# interface.net
KiCad netlist of a schematic drawn in Altium Designer
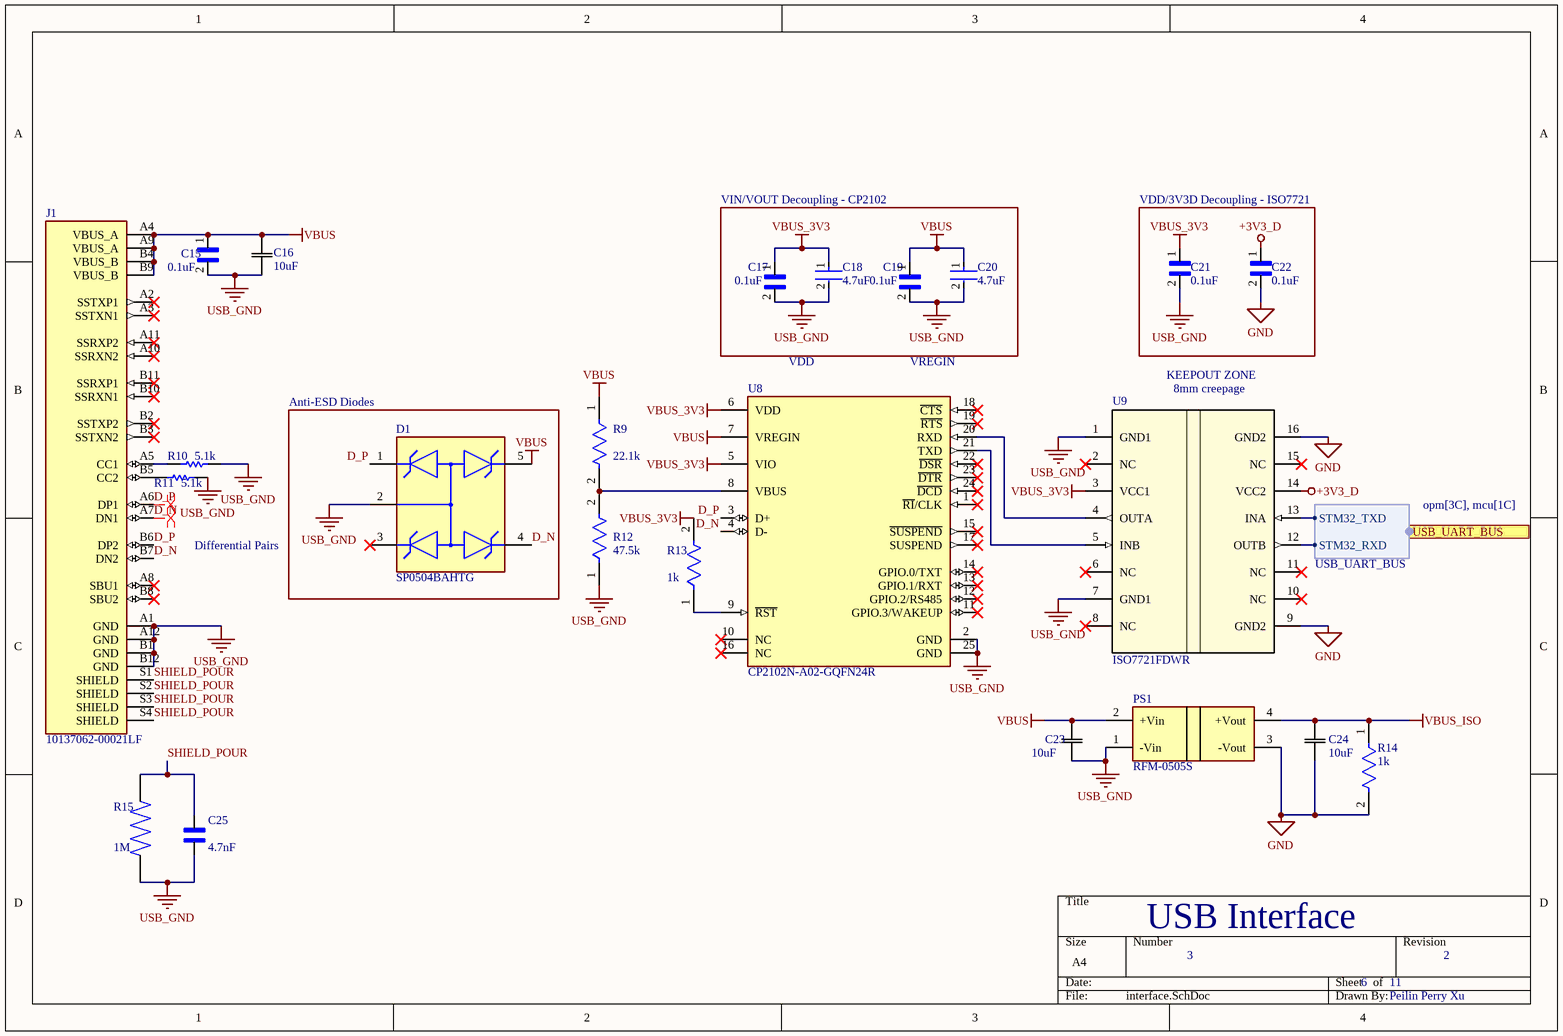
[diagram p0: interface.SchDoc]

(export (version "E")
  (design (tool "Eeschema 10.0.6"))
  (components
    (comp (ref "C15")
      (value "0.1uF")
      (footprint "CC0603JRX7R8BB104")
      (description "25V 100nF X7R ±5% 0603 Multilayer Ceramic Capacitors MLCC - SMD/SMT ROHS")
      (fields
        (field (name "MANUFACTURER") "Yageo Group")
        (field (name "MANUFACTURER PART NUMBER") "CC0603JRX7R8BB104")
      )
      (libsource (lib "opm_lib") (part "CC0603JRX7R8BB104"))
    )
    (comp (ref "C16")
      (value "10uF")
      (footprint "CC0805KKX7R7BB106")
      (description "16V 10uF X7R ±10% 0805 Multilayer Ceramic Capacitors MLCC - SMD/SMT ROHS")
      (fields
        (field (name "MANUFACTURER") "Yageo Group")
        (field (name "MANUFACTURER PART NUMBER") "CC0805KKX7R7BB106")
      )
      (libsource (lib "opm_lib") (part "CC0805KKX7R7BB106"))
    )
    (comp (ref "C17")
      (value "0.1uF")
      (footprint "CC0603JRX7R8BB104")
      (description "25V 100nF X7R ±5% 0603 Multilayer Ceramic Capacitors MLCC - SMD/SMT ROHS")
      (fields
        (field (name "MANUFACTURER") "Yageo Group")
        (field (name "MANUFACTURER PART NUMBER") "CC0603JRX7R8BB104")
      )
      (libsource (lib "opm_lib") (part "CC0603JRX7R8BB104"))
    )
    (comp (ref "C18")
      (value "4.7uF")
      (footprint "CC0805KKX7R7BB106")
      (description "16V 4.7uF X7R ±10% 0805 Multilayer Ceramic Capacitors MLCC - SMD/SMT ROHS")
      (fields
        (field (name "MANUFACTURER") "Yageo Group")
        (field (name "MANUFACTURER PART NUMBER") "CC0805KKX7R7BB475")
      )
      (libsource (lib "opm_lib") (part "CC0805KKX7R7BB475"))
    )
    (comp (ref "C19")
      (value "0.1uF")
      (footprint "CC0603JRX7R8BB104")
      (description "25V 100nF X7R ±5% 0603 Multilayer Ceramic Capacitors MLCC - SMD/SMT ROHS")
      (fields
        (field (name "MANUFACTURER") "Yageo Group")
        (field (name "MANUFACTURER PART NUMBER") "CC0603JRX7R8BB104")
      )
      (libsource (lib "opm_lib") (part "CC0603JRX7R8BB104"))
    )
    (comp (ref "C20")
      (value "4.7uF")
      (footprint "CC0805KKX7R7BB106")
      (description "16V 4.7uF X7R ±10% 0805 Multilayer Ceramic Capacitors MLCC - SMD/SMT ROHS")
      (fields
        (field (name "MANUFACTURER") "Yageo Group")
        (field (name "MANUFACTURER PART NUMBER") "CC0805KKX7R7BB475")
      )
      (libsource (lib "opm_lib") (part "CC0805KKX7R7BB475"))
    )
    (comp (ref "C21")
      (value "0.1uF")
      (footprint "CC0603JRX7R8BB104")
      (description "25V 100nF X7R ±5% 0603 Multilayer Ceramic Capacitors MLCC - SMD/SMT ROHS")
      (fields
        (field (name "MANUFACTURER") "Yageo Group")
        (field (name "MANUFACTURER PART NUMBER") "CC0603JRX7R8BB104")
      )
      (libsource (lib "opm_lib") (part "CC0603JRX7R8BB104"))
    )
    (comp (ref "C22")
      (value "0.1uF")
      (footprint "CC0603JRX7R8BB104")
      (description "25V 100nF X7R ±5% 0603 Multilayer Ceramic Capacitors MLCC - SMD/SMT ROHS")
      (fields
        (field (name "MANUFACTURER") "Yageo Group")
        (field (name "MANUFACTURER PART NUMBER") "CC0603JRX7R8BB104")
      )
      (libsource (lib "opm_lib") (part "CC0603JRX7R8BB104"))
    )
    (comp (ref "C23")
      (value "10uF")
      (footprint "CC0805KKX7R7BB106")
      (description "16V 10uF X7R ±10% 0805 Multilayer Ceramic Capacitors MLCC - SMD/SMT ROHS")
      (fields
        (field (name "MANUFACTURER") "Yageo Group")
        (field (name "MANUFACTURER PART NUMBER") "CC0805KKX7R7BB106")
      )
      (libsource (lib "opm_lib") (part "CC0805KKX7R7BB106"))
    )
    (comp (ref "C24")
      (value "10uF")
      (footprint "CC0805KKX7R7BB106")
      (description "16V 10uF X7R ±10% 0805 Multilayer Ceramic Capacitors MLCC - SMD/SMT ROHS")
      (fields
        (field (name "MANUFACTURER") "Yageo Group")
        (field (name "MANUFACTURER PART NUMBER") "CC0805KKX7R7BB106")
      )
      (libsource (lib "opm_lib") (part "CC0805KKX7R7BB106"))
    )
    (comp (ref "C25")
      (value "4.7nF")
      (footprint "CAPC3216X170N")
      (description "Multilayer Ceramic Capacitor, 4700 pF, 500 V, ± 10%, X7R, 1206 [3216 Metric]")
      (fields
        (field (name "MANUFACTURER") "Vishay")
        (field (name "MANUFACTURER PART NUMBER") "VJ1206Y472KXEAT5Z")
      )
      (libsource (lib "opm_lib") (part "VJ1206Y472KXEAT5Z"))
    )
    (comp (ref "D1")
      (value "SP0504BAHTG")
      (footprint "SP0504BAHTG")
      (description "SP050xBA Series 8 V 30 pF Uni-Directional SMT TVS Avalanche Diode Array SOT-23-5")
      (fields (field (name "MANUFACTURER") "Littelfuse"))
      (libsource (lib "opm_lib") (part "SP0504BAHTG"))
    )
    (comp (ref "J1")
      (value "10137062-00021LF")
      (footprint "AMPHENOL_10137062-00021LF")
      (description "Conn USB Type C Receptacle 24 POS 0.5mm RA Surface Mount/Through Hole Single Port T/R")
      (fields (field (name "MANUFACTURER") "Amphenol Communications Solutions"))
      (libsource (lib "opm_lib") (part "10137062-00021LF"))
    )
    (comp (ref "PS1")
      (value "RFM-0505S")
      (footprint "RFM-0505S")
      (description "DC/DC Converter ; 1W; Vin: 4.5-5.5V; Vout: 5V; Iout: 20mA; -40+85deg.C; THT; SIP4")
      (fields (field (name "MANUFACTURER") "Recom Power"))
      (libsource (lib "opm_lib") (part "RFM-0505S"))
    )
    (comp (ref "R9")
      (value "22.1k")
      (footprint "RC0603FR-07")
      (description "Res General Purpose Thick Film 0603 22.1K Ohm 1% 1/10W ±100ppm/°C Molded SMD Paper T/R")
      (fields
        (field (name "MANUFACTURER") "Yageo Group")
        (field (name "MANUFACTURER PART NUMBER") "RC0603FR-0722K1L")
      )
      (libsource (lib "opm_lib") (part "RC0603FR-0722K1L"))
    )
    (comp (ref "R10")
      (value "5.1k")
      (footprint "RC0603FR-07")
      (description "Res Thick Film 0603 5.1K Ohm 1% 0.1W(1/10W) ±100ppm/C Pad SMD T/R")
      (fields
        (field (name "MANUFACTURER") "Yageo Group")
        (field (name "MANUFACTURER PART NUMBER") "RC0603FR-075K1L")
      )
      (libsource (lib "opm_lib") (part "RC0603FR-075K1L"))
    )
    (comp (ref "R11")
      (value "5.1k")
      (footprint "RC0603FR-07")
      (description "Res Thick Film 0603 5.1K Ohm 1% 0.1W(1/10W) ±100ppm/C Pad SMD T/R")
      (fields
        (field (name "MANUFACTURER") "Yageo Group")
        (field (name "MANUFACTURER PART NUMBER") "RC0603FR-075K1L")
      )
      (libsource (lib "opm_lib") (part "RC0603FR-075K1L"))
    )
    (comp (ref "R12")
      (value "47.5k")
      (footprint "RC0603FR-07")
      (description "100mW Thick Film Resistors 75V ±100ppm/℃ ±1% 47.5kΩ 0603 Chip Resistor - Surface Mount ROHS")
      (fields
        (field (name "MANUFACTURER") "Yageo Group")
        (field (name "MANUFACTURER PART NUMBER") "RC0603FR-0747K5L")
      )
      (libsource (lib "opm_lib") (part "RC0603FR-0747K5L"))
    )
    (comp (ref "R13")
      (value "1k")
      (footprint "RC0603FR-07")
      (description "100mW Thick Film Resistors 75V ±100ppm/℃ ±1% 1kΩ 0603 Chip Resistor - Surface Mount ROHS")
      (fields
        (field (name "MANUFACTURER") "Yageo Group")
        (field (name "MANUFACTURER PART NUMBER") "RC0603FR-071KL")
      )
      (libsource (lib "opm_lib") (part "RC0603FR-071KL"))
    )
    (comp (ref "R14")
      (value "1k")
      (footprint "RC0603FR-07")
      (description "100mW Thick Film Resistors 75V ±100ppm/℃ ±1% 1kΩ 0603 Chip Resistor - Surface Mount ROHS")
      (fields
        (field (name "MANUFACTURER") "Yageo Group")
        (field (name "MANUFACTURER PART NUMBER") "RC0603FR-071KL")
      )
      (libsource (lib "opm_lib") (part "RC0603FR-071KL"))
    )
    (comp (ref "R15")
      (value "1M")
      (footprint "RESC2012X50N")
      (description "Res Thick Film 0805 1M Ohm 1% 0.125W(1/8W) +/-100ppm/ßC Pad SMD Automotive T/R")
      (fields
        (field (name "MANUFACTURER") "Vishay")
        (field (name "MANUFACTURER PART NUMBER") "CRCW08051M00FKEA")
      )
      (libsource (lib "opm_lib") (part "CRCW08051M00FKEA"))
    )
    (comp (ref "U8")
      (value "CP2102N-A02-GQFN24R")
      (footprint "CP2102N-A02-GQFN24R")
      (description "Full Speed USB to UART Bridge USB 2.0 3.3V T/R Automotive Medical 24-Pin QFN EP")
      (fields (field (name "MANUFACTURER") "Silicon Lab"))
      (libsource (lib "opm_lib") (part "CP2102N-A02-GQFN24R"))
    )
    (comp (ref "U9")
      (value "ISO7721FDWR")
      (footprint "ISO7721FDWR")
      (description "Robust EMC, dual-channel, 1/1, reinforced digital isolator 16-SOIC -55 to 125")
      (fields (field (name "MANUFACTURER") "Texas Instruments"))
      (libsource (lib "opm_lib") (part "ISO7721FDWR"))
    )
  )
  (nets
    (net (code "2") (name "+3V3_D") (class "Default")
      (node (ref "C22") (pin "1") (pinfunction "1_1") (pintype "passive"))
      (node (ref "U9") (pin "14") (pinfunction "VCC2_14") (pintype "power_in"))
    )
    (net (code "3") (name "/D_N") (class "Default")
      (node (ref "D1") (pin "4") (pinfunction "4_4") (pintype "passive"))
      (node (ref "J1") (pin "A7") (pinfunction "DN1_A7") (pintype "bidirectional"))
      (node (ref "J1") (pin "B7") (pinfunction "DN2_B7") (pintype "bidirectional"))
      (node (ref "U8") (pin "4") (pinfunction "D-_4") (pintype "bidirectional"))
    )
    (net (code "4") (name "/D_P") (class "Default")
      (node (ref "D1") (pin "1") (pinfunction "1_1") (pintype "passive"))
      (node (ref "J1") (pin "A6") (pinfunction "DP1_A6") (pintype "bidirectional"))
      (node (ref "J1") (pin "B6") (pinfunction "DP2_B6") (pintype "bidirectional"))
      (node (ref "U8") (pin "3") (pinfunction "D+_3") (pintype "bidirectional"))
    )
    (net (code "5") (name "/SHIELD_POUR") (class "Default")
      (node (ref "C25") (pin "2") (pinfunction "2_2") (pintype "passive"))
      (node (ref "J1") (pin "S1") (pinfunction "SHIELD_S1") (pintype "power_in"))
      (node (ref "J1") (pin "S2") (pinfunction "SHIELD_S2") (pintype "power_in"))
      (node (ref "J1") (pin "S3") (pinfunction "SHIELD_S3") (pintype "power_in"))
      (node (ref "J1") (pin "S4") (pinfunction "SHIELD_S4") (pintype "power_in"))
      (node (ref "R15") (pin "2") (pinfunction "2_2") (pintype "passive"))
    )
    (net (code "6") (name "/STM32_RXD") (class "Default")
      (node (ref "U9") (pin "12") (pinfunction "OUTB_12") (pintype "output"))
    )
    (net (code "7") (name "/STM32_TXD") (class "Default")
      (node (ref "U9") (pin "13") (pinfunction "INA_13") (pintype "input"))
    )
    (net (code "9") (name "GND") (class "Default")
      (node (ref "C22") (pin "2") (pinfunction "2_2") (pintype "passive"))
      (node (ref "C24") (pin "1") (pinfunction "1_1") (pintype "passive"))
      (node (ref "PS1") (pin "3") (pinfunction "-Vout_3") (pintype "power_in"))
      (node (ref "R14") (pin "2") (pinfunction "2_2") (pintype "passive"))
      (node (ref "U9") (pin "16") (pinfunction "GND2_16") (pintype "power_in"))
      (node (ref "U9") (pin "9") (pinfunction "GND2_9") (pintype "power_in"))
    )
    (net (code "10") (name "Net-(J1-CC1)") (class "Default")
      (node (ref "J1") (pin "A5") (pinfunction "CC1_A5") (pintype "bidirectional"))
      (node (ref "R10") (pin "1") (pinfunction "1_1") (pintype "passive"))
    )
    (net (code "11") (name "Net-(J1-CC2)") (class "Default")
      (node (ref "J1") (pin "B5") (pinfunction "CC2_B5") (pintype "bidirectional"))
      (node (ref "R11") (pin "1") (pinfunction "1_1") (pintype "passive"))
    )
    (net (code "12") (name "Net-(U8-RXD)") (class "Default")
      (node (ref "U8") (pin "20") (pinfunction "RXD_20") (pintype "input"))
      (node (ref "U9") (pin "4") (pinfunction "OUTA_4") (pintype "output"))
    )
    (net (code "13") (name "Net-(U8-TXD)") (class "Default")
      (node (ref "U8") (pin "21") (pinfunction "TXD_21") (pintype "output"))
      (node (ref "U9") (pin "5") (pinfunction "INB_5") (pintype "input"))
    )
    (net (code "14") (name "Net-(U8-VBUS)") (class "Default")
      (node (ref "R12") (pin "2") (pinfunction "2_2") (pintype "passive"))
      (node (ref "R9") (pin "2") (pinfunction "2_2") (pintype "passive"))
      (node (ref "U8") (pin "8") (pinfunction "VBUS_8") (pintype "power_in"))
    )
    (net (code "15") (name "Net-(U8-~{RST})") (class "Default")
      (node (ref "R13") (pin "1") (pinfunction "1_1") (pintype "passive"))
      (node (ref "U8") (pin "9") (pinfunction "~{RST}_9") (pintype "input"))
    )
    (net (code "16") (name "USB_GND") (class "Default")
      (node (ref "C15") (pin "2") (pinfunction "2_2") (pintype "passive"))
      (node (ref "C16") (pin "1") (pinfunction "1_1") (pintype "passive"))
      (node (ref "C17") (pin "2") (pinfunction "2_2") (pintype "passive"))
      (node (ref "C18") (pin "2") (pinfunction "2_2") (pintype "passive"))
      (node (ref "C19") (pin "2") (pinfunction "2_2") (pintype "passive"))
      (node (ref "C20") (pin "2") (pinfunction "2_2") (pintype "passive"))
      (node (ref "C21") (pin "2") (pinfunction "2_2") (pintype "passive"))
      (node (ref "C23") (pin "1") (pinfunction "1_1") (pintype "passive"))
      (node (ref "C25") (pin "1") (pinfunction "1_1") (pintype "passive"))
      (node (ref "D1") (pin "2") (pinfunction "2_2") (pintype "passive"))
      (node (ref "J1") (pin "A1") (pinfunction "GND_A1") (pintype "power_in"))
      (node (ref "J1") (pin "A12") (pinfunction "GND_A12") (pintype "power_in"))
      (node (ref "J1") (pin "B1") (pinfunction "GND_B1") (pintype "power_in"))
      (node (ref "J1") (pin "B12") (pinfunction "GND_B12") (pintype "power_in"))
      (node (ref "PS1") (pin "1") (pinfunction "-Vin_1") (pintype "power_in"))
      (node (ref "R10") (pin "2") (pinfunction "2_2") (pintype "passive"))
      (node (ref "R11") (pin "2") (pinfunction "2_2") (pintype "passive"))
      (node (ref "R12") (pin "1") (pinfunction "1_1") (pintype "passive"))
      (node (ref "R15") (pin "1") (pinfunction "1_1") (pintype "passive"))
      (node (ref "U8") (pin "2") (pinfunction "GND_2") (pintype "power_in"))
      (node (ref "U8") (pin "25") (pinfunction "GND_25") (pintype "power_in"))
      (node (ref "U9") (pin "1") (pinfunction "GND1_1") (pintype "power_in"))
      (node (ref "U9") (pin "7") (pinfunction "GND1_7") (pintype "power_in"))
    )
    (net (code "17") (name "VBUS") (class "Default")
      (node (ref "C15") (pin "1") (pinfunction "1_1") (pintype "passive"))
      (node (ref "C16") (pin "2") (pinfunction "2_2") (pintype "passive"))
      (node (ref "C19") (pin "1") (pinfunction "1_1") (pintype "passive"))
      (node (ref "C20") (pin "1") (pinfunction "1_1") (pintype "passive"))
      (node (ref "C23") (pin "2") (pinfunction "2_2") (pintype "passive"))
      (node (ref "D1") (pin "5") (pinfunction "5_5") (pintype "passive"))
      (node (ref "J1") (pin "A4") (pinfunction "VBUS_A_A4") (pintype "power_in"))
      (node (ref "J1") (pin "A9") (pinfunction "VBUS_A_A9") (pintype "power_in"))
      (node (ref "J1") (pin "B4") (pinfunction "VBUS_B_B4") (pintype "power_in"))
      (node (ref "J1") (pin "B9") (pinfunction "VBUS_B_B9") (pintype "power_in"))
      (node (ref "PS1") (pin "2") (pinfunction "+Vin_2") (pintype "power_in"))
      (node (ref "R9") (pin "1") (pinfunction "1_1") (pintype "passive"))
      (node (ref "U8") (pin "7") (pinfunction "VREGIN_7") (pintype "power_in"))
    )
    (net (code "18") (name "VBUS_3V3") (class "Default")
      (node (ref "C17") (pin "1") (pinfunction "1_1") (pintype "passive"))
      (node (ref "C18") (pin "1") (pinfunction "1_1") (pintype "passive"))
      (node (ref "C21") (pin "1") (pinfunction "1_1") (pintype "passive"))
      (node (ref "R13") (pin "2") (pinfunction "2_2") (pintype "passive"))
      (node (ref "U8") (pin "5") (pinfunction "VIO_5") (pintype "power_in"))
      (node (ref "U8") (pin "6") (pinfunction "VDD_6") (pintype "power_in"))
      (node (ref "U9") (pin "3") (pinfunction "VCC1_3") (pintype "power_in"))
    )
    (net (code "19") (name "VBUS_ISO") (class "Default")
      (node (ref "C24") (pin "2") (pinfunction "2_2") (pintype "passive"))
      (node (ref "PS1") (pin "4") (pinfunction "+Vout_4") (pintype "power_in"))
      (node (ref "R14") (pin "1") (pinfunction "1_1") (pintype "passive"))
    )
    (net (code "20") (name "unconnected-(D1-Pad3)") (class "Default")
      (node (ref "D1") (pin "3") (pinfunction "3_3") (pintype "passive+no_connect"))
    )
    (net (code "21") (name "unconnected-(J1-SBU1-PadA8)") (class "Default")
      (node (ref "J1") (pin "A8") (pinfunction "SBU1_A8") (pintype "bidirectional+no_connect"))
    )
    (net (code "22") (name "unconnected-(J1-SBU2-PadB8)") (class "Default")
      (node (ref "J1") (pin "B8") (pinfunction "SBU2_B8") (pintype "bidirectional+no_connect"))
    )
    (net (code "23") (name "unconnected-(J1-SSRXN1-PadB10)") (class "Default")
      (node (ref "J1") (pin "B10") (pinfunction "SSRXN1_B10") (pintype "input+no_connect"))
    )
    (net (code "24") (name "unconnected-(J1-SSRXN2-PadA10)") (class "Default")
      (node (ref "J1") (pin "A10") (pinfunction "SSRXN2_A10") (pintype "input+no_connect"))
    )
    (net (code "25") (name "unconnected-(J1-SSRXP1-PadB11)") (class "Default")
      (node (ref "J1") (pin "B11") (pinfunction "SSRXP1_B11") (pintype "input+no_connect"))
    )
    (net (code "26") (name "unconnected-(J1-SSRXP2-PadA11)") (class "Default")
      (node (ref "J1") (pin "A11") (pinfunction "SSRXP2_A11") (pintype "input+no_connect"))
    )
    (net (code "27") (name "unconnected-(J1-SSTXN1-PadA3)") (class "Default")
      (node (ref "J1") (pin "A3") (pinfunction "SSTXN1_A3") (pintype "output+no_connect"))
    )
    (net (code "28") (name "unconnected-(J1-SSTXN2-PadB3)") (class "Default")
      (node (ref "J1") (pin "B3") (pinfunction "SSTXN2_B3") (pintype "output+no_connect"))
    )
    (net (code "29") (name "unconnected-(J1-SSTXP1-PadA2)") (class "Default")
      (node (ref "J1") (pin "A2") (pinfunction "SSTXP1_A2") (pintype "output+no_connect"))
    )
    (net (code "30") (name "unconnected-(J1-SSTXP2-PadB2)") (class "Default")
      (node (ref "J1") (pin "B2") (pinfunction "SSTXP2_B2") (pintype "output+no_connect"))
    )
    (net (code "31") (name "unconnected-(U8-GPIO.0{slash}TXT-Pad14)") (class "Default")
      (node (ref "U8") (pin "14") (pinfunction "GPIO.0/TXT_14") (pintype "bidirectional+no_connect"))
    )
    (net (code "32") (name "unconnected-(U8-GPIO.1{slash}RXT-Pad13)") (class "Default")
      (node (ref "U8") (pin "13") (pinfunction "GPIO.1/RXT_13") (pintype "bidirectional+no_connect"))
    )
    (net (code "33") (name "unconnected-(U8-GPIO.2{slash}RS485-Pad12)") (class "Default")
      (node (ref "U8") (pin "12") (pinfunction "GPIO.2/RS485_12") (pintype "bidirectional+no_connect"))
    )
    (net (code "34") (name "unconnected-(U8-GPIO.3{slash}WAKEUP-Pad11)") (class "Default")
      (node (ref "U8") (pin "11") (pinfunction "GPIO.3/WAKEUP_11") (pintype "bidirectional+no_connect"))
    )
    (net (code "35") (name "unconnected-(U8-NC-Pad10)") (class "Default")
      (node (ref "U8") (pin "10") (pinfunction "NC_10") (pintype "passive+no_connect"))
    )
    (net (code "36") (name "unconnected-(U8-NC-Pad16)") (class "Default")
      (node (ref "U8") (pin "16") (pinfunction "NC_16") (pintype "passive+no_connect"))
    )
    (net (code "37") (name "unconnected-(U8-SUSPEND-Pad17)") (class "Default")
      (node (ref "U8") (pin "17") (pinfunction "SUSPEND_17") (pintype "output+no_connect"))
    )
    (net (code "38") (name "unconnected-(U8-~{CTS}-Pad18)") (class "Default")
      (node (ref "U8") (pin "18") (pinfunction "~{CTS}_18") (pintype "input+no_connect"))
    )
    (net (code "39") (name "unconnected-(U8-~{DCD}-Pad24)") (class "Default")
      (node (ref "U8") (pin "24") (pinfunction "~{DCD}_24") (pintype "input+no_connect"))
    )
    (net (code "40") (name "unconnected-(U8-~{DSR}-Pad22)") (class "Default")
      (node (ref "U8") (pin "22") (pinfunction "~{DSR}_22") (pintype "input+no_connect"))
    )
    (net (code "41") (name "unconnected-(U8-~{DTR}-Pad23)") (class "Default")
      (node (ref "U8") (pin "23") (pinfunction "~{DTR}_23") (pintype "output+no_connect"))
    )
    (net (code "42") (name "unconnected-(U8-~{RI}{slash}CLK-Pad1)") (class "Default")
      (node (ref "U8") (pin "1") (pinfunction "~{RI}/CLK_1") (pintype "input+no_connect"))
    )
    (net (code "43") (name "unconnected-(U8-~{RTS}-Pad19)") (class "Default")
      (node (ref "U8") (pin "19") (pinfunction "~{RTS}_19") (pintype "output+no_connect"))
    )
    (net (code "44") (name "unconnected-(U8-~{SUSPEND}-Pad15)") (class "Default")
      (node (ref "U8") (pin "15") (pinfunction "~{SUSPEND}_15") (pintype "output+no_connect"))
    )
    (net (code "45") (name "unconnected-(U9-NC-Pad2)") (class "Default")
      (node (ref "U9") (pin "2") (pinfunction "NC_2") (pintype "passive+no_connect"))
    )
    (net (code "46") (name "unconnected-(U9-NC-Pad6)") (class "Default")
      (node (ref "U9") (pin "6") (pinfunction "NC_6") (pintype "passive+no_connect"))
    )
    (net (code "47") (name "unconnected-(U9-NC-Pad8)") (class "Default")
      (node (ref "U9") (pin "8") (pinfunction "NC_8") (pintype "passive+no_connect"))
    )
    (net (code "48") (name "unconnected-(U9-NC-Pad10)") (class "Default")
      (node (ref "U9") (pin "10") (pinfunction "NC_10") (pintype "passive+no_connect"))
    )
    (net (code "49") (name "unconnected-(U9-NC-Pad11)") (class "Default")
      (node (ref "U9") (pin "11") (pinfunction "NC_11") (pintype "passive+no_connect"))
    )
    (net (code "50") (name "unconnected-(U9-NC-Pad15)") (class "Default")
      (node (ref "U9") (pin "15") (pinfunction "NC_15") (pintype "passive+no_connect"))
    )
  )
)
